# 03-PSU-ps2-blueretro.net
KiCad netlist of a schematic drawn in Altium Designer
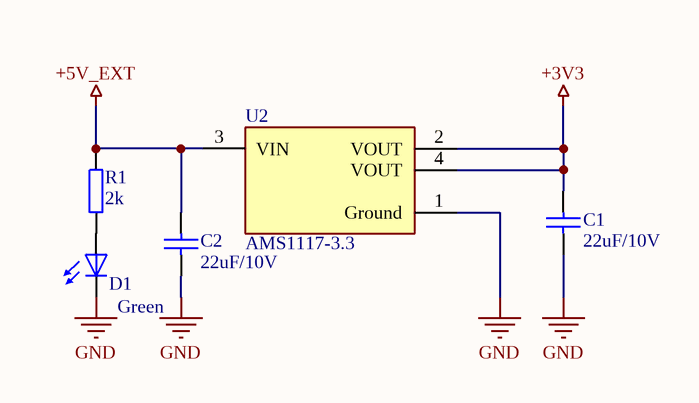
[diagram p0: 03-PSU-ps2-blueretro.SchDoc]

(export (version "E")
  (design (tool "Eeschema 10.0.6"))
  (components
    (comp (ref "C1")
      (value "22uF/10V")
      (footprint "cap_0603")
      (fields (field (name "Comment") "cap_0603"))
      (libsource (lib "mycomponents") (part "cap_0603"))
    )
    (comp (ref "C2")
      (value "22uF/10V")
      (footprint "cap_0603")
      (fields (field (name "Comment") "cap_0603"))
      (libsource (lib "mycomponents") (part "cap_0603"))
    )
    (comp (ref "D1")
      (value "Green")
      (footprint "led0603_GREEN")
      (description "Green 3,2V 20mA")
      (fields
        (field (name "MANUFACTURER") "Würth Elektronik")
        (field (name "MANUFACTURER PART NUMBER") "150060GS75000")
      )
      (libsource (lib "mycomponents") (part "led_0603"))
    )
    (comp (ref "R1")
      (value "2k")
      (footprint "res_0603")
      (fields (field (name "Comment") "res_0603"))
      (libsource (lib "mycomponents") (part "res_0603"))
    )
    (comp (ref "U2")
      (value "AMS1117-3.3")
      (footprint "FP-AMS1117-IPC_C")
      (description "LDO Voltage Regulators 1A, 3.3V")
      (fields
        (field (name "OCTOPART") "https://octopart.com/ams1117-3.3-advanced+monolithic+systems-25899300")
        (field (name "MANUFACTURER") "Advanced Monolithic Systems")
      )
      (libsource (lib "Altium Content Vault") (part "8bdbb5f8e77002000e30dd2845d0354"))
    )
  )
  (nets
    (net (code "1") (name "+3V3") (class "Default")
      (node (ref "C1") (pin "2") (pinfunction "2_2") (pintype "passive"))
      (node (ref "U2") (pin "2") (pinfunction "VOUT_2") (pintype "passive"))
      (node (ref "U2") (pin "4") (pinfunction "VOUT_4") (pintype "passive"))
    )
    (net (code "2") (name "+5V_EXT") (class "Default")
      (node (ref "C2") (pin "2") (pinfunction "2_2") (pintype "passive"))
      (node (ref "R1") (pin "2") (pinfunction "2_2") (pintype "passive"))
      (node (ref "U2") (pin "3") (pinfunction "VIN_3") (pintype "power_in"))
    )
    (net (code "3") (name "GND") (class "Default")
      (node (ref "C1") (pin "1") (pinfunction "1_1") (pintype "passive"))
      (node (ref "C2") (pin "1") (pinfunction "1_1") (pintype "passive"))
      (node (ref "D1") (pin "2") (pinfunction "C_2") (pintype "passive"))
      (node (ref "U2") (pin "1") (pinfunction "Ground_1") (pintype "power_in"))
    )
    (net (code "4") (name "Net-(D1-A)") (class "Default")
      (node (ref "D1") (pin "1") (pinfunction "A_1") (pintype "passive"))
      (node (ref "R1") (pin "1") (pinfunction "1_1") (pintype "passive"))
    )
  )
)
